# pcb2.net
KiCad netlist of a schematic drawn in EAGLE
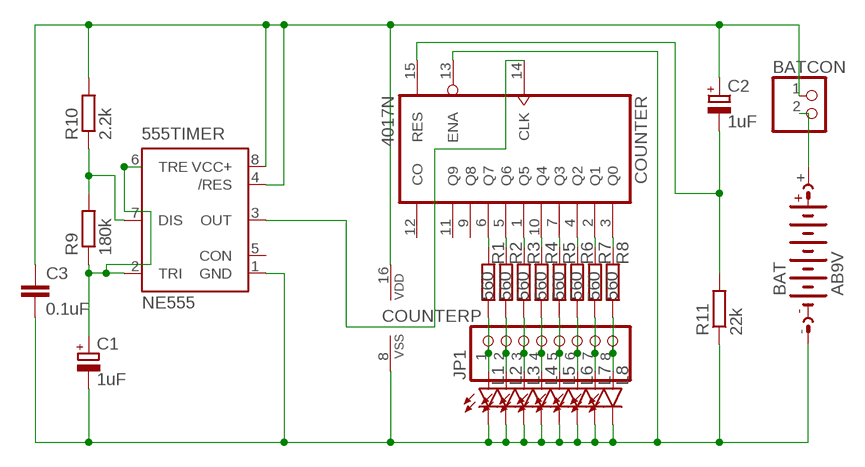
[diagram p0: schematic, sheet 1]

(export (version "E")
  (design (tool "Eeschema 10.0.6"))
  (components
    (comp (ref "555TIMER")
      (value "NE555")
      (footprint "eagle-import:DIL-08")
      (fields (field (name "MF") "Arrow Electronics") (field (name "MPN") "NE555N"))
      (libsource (lib "eagle-import") (part "NE555"))
    )
    (comp (ref "BAT")
      (value "AB9V")
      (footprint "eagle-import:AB9V")
      (libsource (lib "eagle-import") (part "AB9V"))
    )
    (comp (ref "BATCON")
      (value "PINHD-1X2")
      (footprint "eagle-import:1X02")
      (libsource (lib "eagle-import") (part "PINHD-1X2"))
    )
    (comp (ref "C1")
      (value "1uF")
      (footprint "eagle-import:E2,5-5")
      (libsource (lib "eagle-import") (part "CPOL-EUE2.5-5"))
    )
    (comp (ref "C2")
      (value "1uF")
      (footprint "eagle-import:E2,5-5")
      (libsource (lib "eagle-import") (part "CPOL-EUE2.5-5"))
    )
    (comp (ref "C3")
      (value "0.1uF")
      (footprint "eagle-import:C050-024X044")
      (libsource (lib "eagle-import") (part "C-EU050-024X044"))
    )
    (comp (ref "COUNTER")
      (value "4017N")
      (footprint "eagle-import:DIL16")
      (libsource (lib "eagle-import") (part "4017N"))
    )
    (comp (ref "JP1")
      (value "PINHD-1X8")
      (footprint "eagle-import:1X08")
      (libsource (lib "eagle-import") (part "PINHD-1X8"))
    )
    (comp (ref "L1")
      (value "LED5MM")
      (footprint "eagle-import:LED5MM")
      (libsource (lib "eagle-import") (part "LED5MM"))
    )
    (comp (ref "L2")
      (value "LED5MM")
      (footprint "eagle-import:LED5MM")
      (libsource (lib "eagle-import") (part "LED5MM"))
    )
    (comp (ref "L3")
      (value "LED5MM")
      (footprint "eagle-import:LED5MM")
      (libsource (lib "eagle-import") (part "LED5MM"))
    )
    (comp (ref "L4")
      (value "LED5MM")
      (footprint "eagle-import:LED5MM")
      (libsource (lib "eagle-import") (part "LED5MM"))
    )
    (comp (ref "L5")
      (value "LED5MM")
      (footprint "eagle-import:LED5MM")
      (libsource (lib "eagle-import") (part "LED5MM"))
    )
    (comp (ref "L6")
      (value "LED5MM")
      (footprint "eagle-import:LED5MM")
      (libsource (lib "eagle-import") (part "LED5MM"))
    )
    (comp (ref "L7")
      (value "LED5MM")
      (footprint "eagle-import:LED5MM")
      (libsource (lib "eagle-import") (part "LED5MM"))
    )
    (comp (ref "L8")
      (value "LED5MM")
      (footprint "eagle-import:LED5MM")
      (libsource (lib "eagle-import") (part "LED5MM"))
    )
    (comp (ref "R1")
      (value "560")
      (footprint "eagle-import:0207_10")
      (libsource (lib "eagle-import") (part "R-EU_0207/10"))
    )
    (comp (ref "R2")
      (value "560")
      (footprint "eagle-import:0207_10")
      (libsource (lib "eagle-import") (part "R-EU_0207/10"))
    )
    (comp (ref "R3")
      (value "560")
      (footprint "eagle-import:0207_10")
      (libsource (lib "eagle-import") (part "R-EU_0207/10"))
    )
    (comp (ref "R4")
      (value "560")
      (footprint "eagle-import:0207_10")
      (libsource (lib "eagle-import") (part "R-EU_0207/10"))
    )
    (comp (ref "R5")
      (value "560")
      (footprint "eagle-import:0207_10")
      (libsource (lib "eagle-import") (part "R-EU_0207/10"))
    )
    (comp (ref "R6")
      (value "560")
      (footprint "eagle-import:0207_10")
      (libsource (lib "eagle-import") (part "R-EU_0207/10"))
    )
    (comp (ref "R7")
      (value "560")
      (footprint "eagle-import:0207_10")
      (libsource (lib "eagle-import") (part "R-EU_0207/10"))
    )
    (comp (ref "R8")
      (value "560")
      (footprint "eagle-import:0207_10")
      (libsource (lib "eagle-import") (part "R-EU_0207/10"))
    )
    (comp (ref "R9")
      (value "180k")
      (footprint "eagle-import:0207_10")
      (libsource (lib "eagle-import") (part "R-EU_0207/10"))
    )
    (comp (ref "R10")
      (value "2.2k")
      (footprint "eagle-import:0207_10")
      (libsource (lib "eagle-import") (part "R-EU_0207/10"))
    )
    (comp (ref "R11")
      (value "22k")
      (footprint "eagle-import:0207_10")
      (libsource (lib "eagle-import") (part "R-EU_0207/10"))
    )
  )
  (nets
    (net (code "1") (name "Net-(555TIMER-DIS)") (class "Default")
      (node (ref "555TIMER") (pin "7") (pinfunction "DIS_7") (pintype "input"))
      (node (ref "R10") (pin "1") (pinfunction "1_1") (pintype "passive"))
      (node (ref "R9") (pin "2") (pinfunction "2_2") (pintype "passive"))
    )
    (net (code "2") (name "Net-(555TIMER-GND)") (class "Default")
      (node (ref "555TIMER") (pin "1") (pinfunction "GND_1") (pintype "power_in"))
      (node (ref "BAT") (pin "-") (pinfunction "-_-") (pintype "passive"))
      (node (ref "C1") (pin "-") (pinfunction "-_-") (pintype "passive"))
      (node (ref "C3") (pin "2") (pinfunction "2_2") (pintype "passive"))
      (node (ref "COUNTER") (pin "13") (pinfunction "ENA_13") (pintype "input"))
      (node (ref "COUNTER") (pin "8") (pinfunction "VSS_8") (pintype "power_in"))
      (node (ref "L1") (pin "K") (pinfunction "C_K") (pintype "passive"))
      (node (ref "L2") (pin "K") (pinfunction "C_K") (pintype "passive"))
      (node (ref "L3") (pin "K") (pinfunction "C_K") (pintype "passive"))
      (node (ref "L4") (pin "K") (pinfunction "C_K") (pintype "passive"))
      (node (ref "L5") (pin "K") (pinfunction "C_K") (pintype "passive"))
      (node (ref "L6") (pin "K") (pinfunction "C_K") (pintype "passive"))
      (node (ref "L7") (pin "K") (pinfunction "C_K") (pintype "passive"))
      (node (ref "L8") (pin "K") (pinfunction "C_K") (pintype "passive"))
      (node (ref "R11") (pin "1") (pinfunction "1_1") (pintype "passive"))
    )
    (net (code "3") (name "Net-(555TIMER-OUT)") (class "Default")
      (node (ref "555TIMER") (pin "3") (pinfunction "OUT_3") (pintype "output"))
      (node (ref "COUNTER") (pin "14") (pinfunction "CLK_14") (pintype "input"))
    )
    (net (code "4") (name "Net-(555TIMER-TRE)") (class "Default")
      (node (ref "555TIMER") (pin "2") (pinfunction "TRI_2") (pintype "input"))
      (node (ref "555TIMER") (pin "6") (pinfunction "TRE_6") (pintype "input"))
      (node (ref "C1") (pin "+") (pinfunction "+_+") (pintype "passive"))
      (node (ref "R9") (pin "1") (pinfunction "1_1") (pintype "passive"))
    )
    (net (code "5") (name "Net-(555TIMER-VCC+)") (class "Default")
      (node (ref "555TIMER") (pin "4") (pinfunction "/RES_4") (pintype "input"))
      (node (ref "555TIMER") (pin "8") (pinfunction "VCC+_8") (pintype "power_in"))
      (node (ref "BATCON") (pin "1") (pinfunction "1_1") (pintype "passive"))
      (node (ref "C2") (pin "+") (pinfunction "+_+") (pintype "passive"))
      (node (ref "C3") (pin "1") (pinfunction "1_1") (pintype "passive"))
      (node (ref "COUNTER") (pin "16") (pinfunction "VDD_16") (pintype "power_in"))
      (node (ref "R10") (pin "2") (pinfunction "2_2") (pintype "passive"))
    )
    (net (code "6") (name "Net-(BAT-Pad+)") (class "Default")
      (node (ref "BAT") (pin "+") (pinfunction "+_+") (pintype "passive"))
      (node (ref "BATCON") (pin "2") (pinfunction "2_2") (pintype "passive"))
    )
    (net (code "7") (name "Net-(COUNTERA-Q0)") (class "Default")
      (node (ref "COUNTER") (pin "3") (pinfunction "Q0_3") (pintype "output"))
      (node (ref "R8") (pin "2") (pinfunction "2_2") (pintype "passive"))
    )
    (net (code "8") (name "Net-(COUNTERA-Q1)") (class "Default")
      (node (ref "COUNTER") (pin "2") (pinfunction "Q1_2") (pintype "output"))
      (node (ref "R7") (pin "2") (pinfunction "2_2") (pintype "passive"))
    )
    (net (code "9") (name "Net-(COUNTERA-Q2)") (class "Default")
      (node (ref "COUNTER") (pin "4") (pinfunction "Q2_4") (pintype "output"))
      (node (ref "R6") (pin "2") (pinfunction "2_2") (pintype "passive"))
    )
    (net (code "10") (name "Net-(COUNTERA-Q3)") (class "Default")
      (node (ref "COUNTER") (pin "7") (pinfunction "Q3_7") (pintype "output"))
      (node (ref "R5") (pin "2") (pinfunction "2_2") (pintype "passive"))
    )
    (net (code "11") (name "Net-(COUNTERA-Q4)") (class "Default")
      (node (ref "COUNTER") (pin "10") (pinfunction "Q4_10") (pintype "output"))
      (node (ref "R4") (pin "2") (pinfunction "2_2") (pintype "passive"))
    )
    (net (code "12") (name "Net-(COUNTERA-Q5)") (class "Default")
      (node (ref "COUNTER") (pin "1") (pinfunction "Q5_1") (pintype "output"))
      (node (ref "R3") (pin "2") (pinfunction "2_2") (pintype "passive"))
    )
    (net (code "13") (name "Net-(COUNTERA-Q6)") (class "Default")
      (node (ref "COUNTER") (pin "5") (pinfunction "Q6_5") (pintype "output"))
      (node (ref "R2") (pin "2") (pinfunction "2_2") (pintype "passive"))
    )
    (net (code "14") (name "Net-(COUNTERA-Q7)") (class "Default")
      (node (ref "COUNTER") (pin "6") (pinfunction "Q7_6") (pintype "output"))
      (node (ref "R1") (pin "2") (pinfunction "2_2") (pintype "passive"))
    )
    (net (code "15") (name "Net-(COUNTERA-RES)") (class "Default")
      (node (ref "C2") (pin "-") (pinfunction "-_-") (pintype "passive"))
      (node (ref "COUNTER") (pin "15") (pinfunction "RES_15") (pintype "input"))
      (node (ref "R11") (pin "2") (pinfunction "2_2") (pintype "passive"))
    )
    (net (code "16") (name "Net-(JP1-Pad1)") (class "Default")
      (node (ref "JP1") (pin "1") (pinfunction "1_1") (pintype "passive"))
      (node (ref "L1") (pin "A") (pinfunction "A_A") (pintype "passive"))
      (node (ref "R1") (pin "1") (pinfunction "1_1") (pintype "passive"))
    )
    (net (code "17") (name "Net-(JP1-Pad2)") (class "Default")
      (node (ref "JP1") (pin "2") (pinfunction "2_2") (pintype "passive"))
      (node (ref "L2") (pin "A") (pinfunction "A_A") (pintype "passive"))
      (node (ref "R2") (pin "1") (pinfunction "1_1") (pintype "passive"))
    )
    (net (code "18") (name "Net-(JP1-Pad3)") (class "Default")
      (node (ref "JP1") (pin "3") (pinfunction "3_3") (pintype "passive"))
      (node (ref "L3") (pin "A") (pinfunction "A_A") (pintype "passive"))
      (node (ref "R3") (pin "1") (pinfunction "1_1") (pintype "passive"))
    )
    (net (code "19") (name "Net-(JP1-Pad4)") (class "Default")
      (node (ref "JP1") (pin "4") (pinfunction "4_4") (pintype "passive"))
      (node (ref "L4") (pin "A") (pinfunction "A_A") (pintype "passive"))
      (node (ref "R4") (pin "1") (pinfunction "1_1") (pintype "passive"))
    )
    (net (code "20") (name "Net-(JP1-Pad5)") (class "Default")
      (node (ref "JP1") (pin "5") (pinfunction "5_5") (pintype "passive"))
      (node (ref "L5") (pin "A") (pinfunction "A_A") (pintype "passive"))
      (node (ref "R5") (pin "1") (pinfunction "1_1") (pintype "passive"))
    )
    (net (code "21") (name "Net-(JP1-Pad6)") (class "Default")
      (node (ref "JP1") (pin "6") (pinfunction "6_6") (pintype "passive"))
      (node (ref "L6") (pin "A") (pinfunction "A_A") (pintype "passive"))
      (node (ref "R6") (pin "1") (pinfunction "1_1") (pintype "passive"))
    )
    (net (code "22") (name "Net-(JP1-Pad7)") (class "Default")
      (node (ref "JP1") (pin "7") (pinfunction "7_7") (pintype "passive"))
      (node (ref "L7") (pin "A") (pinfunction "A_A") (pintype "passive"))
      (node (ref "R7") (pin "1") (pinfunction "1_1") (pintype "passive"))
    )
    (net (code "23") (name "Net-(JP1-Pad8)") (class "Default")
      (node (ref "JP1") (pin "8") (pinfunction "8_8") (pintype "passive"))
      (node (ref "L8") (pin "A") (pinfunction "A_A") (pintype "passive"))
      (node (ref "R8") (pin "1") (pinfunction "1_1") (pintype "passive"))
    )
    (net (code "24") (name "unconnected-(555TIMER-CON-Pad5)") (class "Default")
      (node (ref "555TIMER") (pin "5") (pinfunction "CON_5") (pintype "input"))
    )
    (net (code "25") (name "unconnected-(COUNTERA-CO-Pad12)") (class "Default")
      (node (ref "COUNTER") (pin "12") (pinfunction "CO_12") (pintype "output"))
    )
    (net (code "26") (name "unconnected-(COUNTERA-Q8-Pad9)") (class "Default")
      (node (ref "COUNTER") (pin "9") (pinfunction "Q8_9") (pintype "output"))
    )
    (net (code "27") (name "unconnected-(COUNTERA-Q9-Pad11)") (class "Default")
      (node (ref "COUNTER") (pin "11") (pinfunction "Q9_11") (pintype "output"))
    )
  )
)
